# thread_dongle.net
KiCad netlist of a schematic drawn in EAGLE
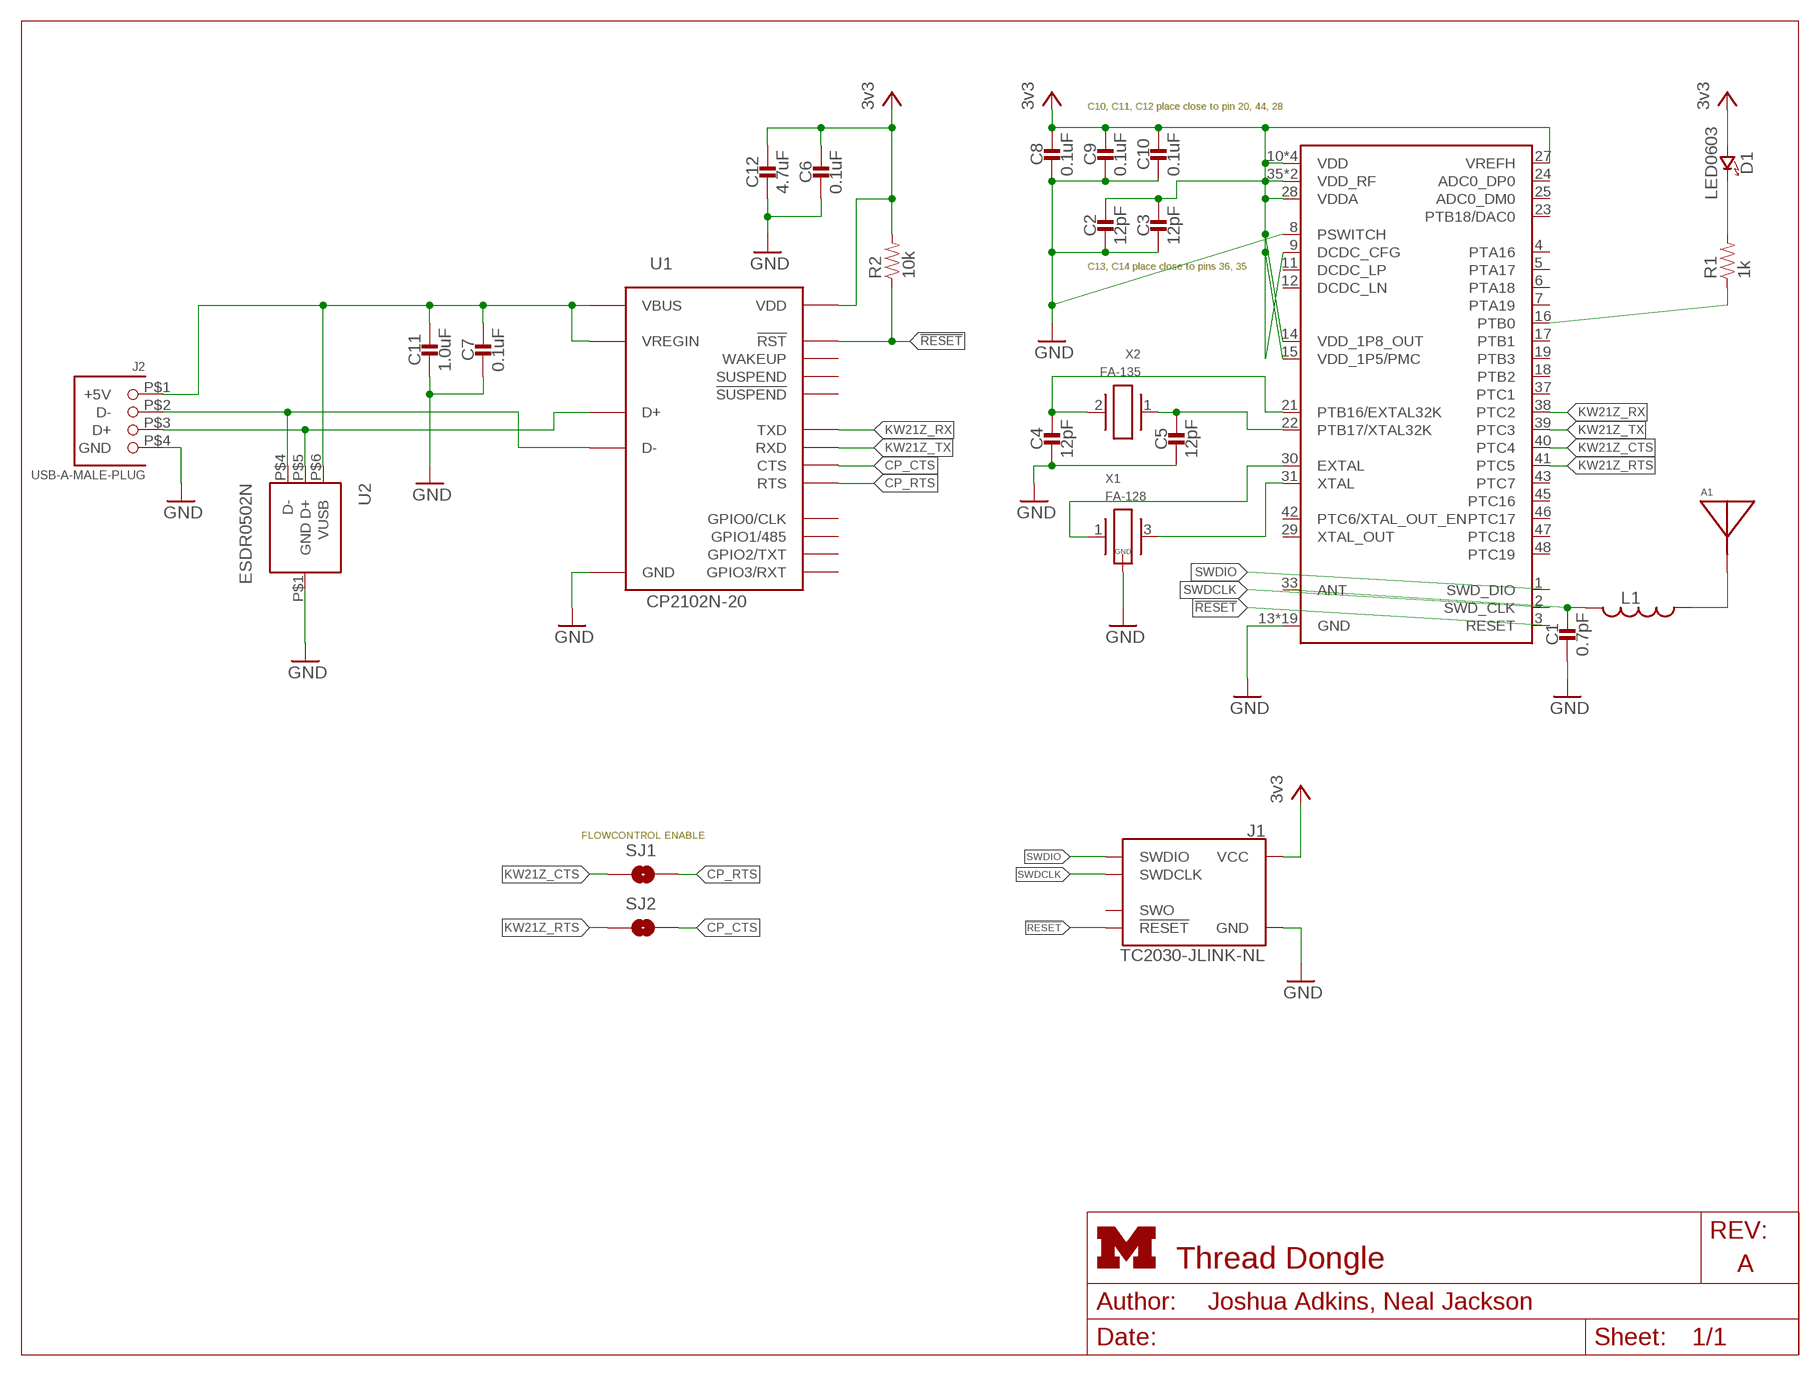
[diagram p0: schematic, sheet 1]

(export (version "E")
  (design (tool "Eeschema 10.0.6"))
  (components
    (comp (ref "A1")
      (value "AH212M")
      (footprint "eagle-import:AH212M")
      (libsource (lib "eagle-import") (part "AH212M"))
    )
    (comp (ref "C1")
      (value "0.7pF")
      (footprint "eagle-import:0402_CAP")
      (fields (field (name "MPN") "GRM1555C1HR70BA01D"))
      (libsource (lib "eagle-import") (part "CAPACITOR0402_CAP"))
    )
    (comp (ref "C2")
      (value "12pF")
      (footprint "eagle-import:0402_CAP")
      (fields (field (name "MPN") "GRM1555C1H120JA01D"))
      (libsource (lib "eagle-import") (part "CAPACITOR0402_CAP"))
    )
    (comp (ref "C3")
      (value "12pF")
      (footprint "eagle-import:0402_CAP")
      (fields (field (name "MPN") "GRM1555C1H120JA01D"))
      (libsource (lib "eagle-import") (part "CAPACITOR0402_CAP"))
    )
    (comp (ref "C4")
      (value "12pF")
      (footprint "eagle-import:0402_CAP")
      (fields (field (name "MPN") "GRM1555C1H120JA01D"))
      (libsource (lib "eagle-import") (part "CAPACITOR0402_CAP"))
    )
    (comp (ref "C5")
      (value "12pF")
      (footprint "eagle-import:0402_CAP")
      (fields (field (name "MPN") "GRM1555C1H120JA01D"))
      (libsource (lib "eagle-import") (part "CAPACITOR0402_CAP"))
    )
    (comp (ref "C6")
      (value "0.1uF")
      (footprint "eagle-import:0402_CAP")
      (fields (field (name "MPN") "LMK105BJ104KV-F"))
      (libsource (lib "eagle-import") (part "CAPACITOR0402_CAP"))
    )
    (comp (ref "C7")
      (value "0.1uF")
      (footprint "eagle-import:0402_CAP")
      (fields (field (name "MPN") "LMK105BJ104KV-F"))
      (libsource (lib "eagle-import") (part "CAPACITOR0402_CAP"))
    )
    (comp (ref "C8")
      (value "0.1uF")
      (footprint "eagle-import:0402_CAP")
      (fields (field (name "MPN") "LMK105BJ104KV-F"))
      (libsource (lib "eagle-import") (part "CAPACITOR0402_CAP"))
    )
    (comp (ref "C9")
      (value "0.1uF")
      (footprint "eagle-import:0402_CAP")
      (fields (field (name "MPN") "LMK105BJ104KV-F"))
      (libsource (lib "eagle-import") (part "CAPACITOR0402_CAP"))
    )
    (comp (ref "C10")
      (value "0.1uF")
      (footprint "eagle-import:0402_CAP")
      (fields (field (name "MPN") "LMK105BJ104KV-F"))
      (libsource (lib "eagle-import") (part "CAPACITOR0402_CAP"))
    )
    (comp (ref "C11")
      (value "1.0uF")
      (footprint "eagle-import:0402_CAP")
      (fields (field (name "MPN") "GRM155R61E105MA12D"))
      (libsource (lib "eagle-import") (part "CAPACITOR0402_CAP"))
    )
    (comp (ref "C12")
      (value "4.7uF")
      (footprint "eagle-import:0402_CAP")
      (fields (field (name "MPN") "GRM155R60J475ME47D"))
      (libsource (lib "eagle-import") (part "CAPACITOR0402_CAP"))
    )
    (comp (ref "D1")
      (value "LED0603")
      (footprint "eagle-import:LED-0603")
      (fields (field (name "MPN") "LTST-C194TBKT"))
      (libsource (lib "eagle-import") (part "LED0603"))
    )
    (comp (ref "J1")
      (value "TC2030-JLINK-NL")
      (footprint "eagle-import:TC2030-IDC-NL")
      (libsource (lib "eagle-import") (part "TC2030-JLINK-NL"))
    )
    (comp (ref "J2")
      (value "USB-A-MALE-PLUG")
      (footprint "eagle-import:USB_A_MALE_PLUG_CUI_UP2-AH")
      (fields (field (name "MANUFACTURER") "CUI") (field (name "MPN") "UP2-AH-1-TH"))
      (libsource (lib "eagle-import") (part "USB-A-MALE-PLUG"))
    )
    (comp (ref "L1")
      (value "INDUCTOR0402")
      (footprint "eagle-import:0402_CAP")
      (fields (field (name "MPN") "LQG15HS5N1S02D"))
      (libsource (lib "eagle-import") (part "INDUCTOR0402"))
    )
    (comp (ref "R1")
      (value "1k")
      (footprint "eagle-import:0402_RES")
      (fields (field (name "MPN") "RC0402JR-071KL"))
      (libsource (lib "eagle-import") (part "RESISTOR0402_RES"))
    )
    (comp (ref "R2")
      (value "10k")
      (footprint "eagle-import:0402_RES")
      (fields (field (name "MPN") "RC0402JR-0710KL"))
      (libsource (lib "eagle-import") (part "RESISTOR0402_RES"))
    )
    (comp (ref "SJ1")
      (value "SOLDERJUMPERNC")
      (footprint "eagle-import:SJ_2S_SMALL")
      (libsource (lib "eagle-import") (part "SOLDERJUMPERNC"))
    )
    (comp (ref "SJ2")
      (value "SOLDERJUMPERNC")
      (footprint "eagle-import:SJ_2S_SMALL")
      (libsource (lib "eagle-import") (part "SOLDERJUMPERNC"))
    )
    (comp (ref "U1")
      (value "CP2102N-20")
      (footprint "eagle-import:QFN-20-3MM")
      (fields (field (name "MANUFACTURER") "SiLabs") (field (name "MPN") "CP2102N-A01-GQFN20"))
      (libsource (lib "eagle-import") (part "CP2102N-20"))
    )
    (comp (ref "U2")
      (value "ESDR0502N")
      (footprint "eagle-import:UDFN-6")
      (libsource (lib "eagle-import") (part "ESDR0502N"))
    )
    (comp (ref "U3")
      (value "KW21Z")
      (footprint "eagle-import:LAMINATE-QFN-48-7MM")
      (fields (field (name "MPN") "MKW21Z256VHT4"))
      (libsource (lib "eagle-import") (part "KW21Z"))
    )
    (comp (ref "X1")
      (value "FA-128")
      (footprint "eagle-import:FA-128")
      (fields (field (name "MPN") "FA-128 32.0000MF20X-K5"))
      (libsource (lib "eagle-import") (part "FA-128"))
    )
    (comp (ref "X2")
      (value "FA-135")
      (footprint "eagle-import:FC-135")
      (fields (field (name "MPN") "FC-135 32.7680KA-AG3"))
      (libsource (lib "eagle-import") (part "FA-135"))
    )
  )
  (nets
    (net (code "1") (name "/~{RESET}") (class "Default")
      (node (ref "J1") (pin "3") (pinfunction "~{RESET}_3") (pintype "bidirectional"))
      (node (ref "R2") (pin "1") (pinfunction "1_1") (pintype "passive"))
      (node (ref "U1") (pin "9") (pinfunction "~{RST}_9") (pintype "bidirectional"))
      (node (ref "U3") (pin "3") (pinfunction "RESET_3") (pintype "bidirectional"))
    )
    (net (code "2") (name "3v3") (class "Default")
      (node (ref "C10") (pin "1") (pinfunction "1_1") (pintype "bidirectional"))
      (node (ref "C12") (pin "1") (pinfunction "1_1") (pintype "bidirectional"))
      (node (ref "C2") (pin "1") (pinfunction "1_1") (pintype "bidirectional"))
      (node (ref "C3") (pin "1") (pinfunction "1_1") (pintype "bidirectional"))
      (node (ref "C6") (pin "1") (pinfunction "1_1") (pintype "bidirectional"))
      (node (ref "C8") (pin "1") (pinfunction "1_1") (pintype "bidirectional"))
      (node (ref "C9") (pin "1") (pinfunction "1_1") (pintype "bidirectional"))
      (node (ref "D1") (pin "A") (pinfunction "ANODE_A") (pintype "bidirectional"))
      (node (ref "J1") (pin "1") (pinfunction "VCC_1") (pintype "bidirectional"))
      (node (ref "R2") (pin "2") (pinfunction "2_2") (pintype "passive"))
      (node (ref "U1") (pin "6") (pinfunction "VDD_6") (pintype "bidirectional"))
      (node (ref "U3") (pin "10") (pinfunction "VDD_10") (pintype "bidirectional"))
      (node (ref "U3") (pin "14") (pinfunction "VDD_1P8_OUT_14") (pintype "bidirectional"))
      (node (ref "U3") (pin "15") (pinfunction "VDD_1P5/PMC_15") (pintype "bidirectional"))
      (node (ref "U3") (pin "20") (pinfunction "VDD_20") (pintype "bidirectional"))
      (node (ref "U3") (pin "27") (pinfunction "VREFH_27") (pintype "bidirectional"))
      (node (ref "U3") (pin "28") (pinfunction "VDDA_28") (pintype "bidirectional"))
      (node (ref "U3") (pin "32") (pinfunction "VDD_32") (pintype "bidirectional"))
      (node (ref "U3") (pin "35") (pinfunction "VDD_RF_35") (pintype "bidirectional"))
      (node (ref "U3") (pin "36") (pinfunction "VDD_RF_36") (pintype "bidirectional"))
      (node (ref "U3") (pin "44") (pinfunction "VDD_44") (pintype "bidirectional"))
      (node (ref "U3") (pin "9") (pinfunction "DCDC_CFG_9") (pintype "bidirectional"))
    )
    (net (code "3") (name "CP_CTS") (class "Default")
      (node (ref "SJ2") (pin "2") (pinfunction "2_2") (pintype "passive"))
      (node (ref "U1") (pin "15") (pinfunction "CTS_15") (pintype "bidirectional"))
    )
    (net (code "4") (name "CP_RTS") (class "Default")
      (node (ref "SJ1") (pin "2") (pinfunction "2_2") (pintype "passive"))
      (node (ref "U1") (pin "16") (pinfunction "RTS_16") (pintype "bidirectional"))
    )
    (net (code "5") (name "GND") (class "Default")
      (node (ref "C1") (pin "2") (pinfunction "2_2") (pintype "bidirectional"))
      (node (ref "C10") (pin "2") (pinfunction "2_2") (pintype "bidirectional"))
      (node (ref "C11") (pin "2") (pinfunction "2_2") (pintype "bidirectional"))
      (node (ref "C12") (pin "2") (pinfunction "2_2") (pintype "bidirectional"))
      (node (ref "C2") (pin "2") (pinfunction "2_2") (pintype "bidirectional"))
      (node (ref "C3") (pin "2") (pinfunction "2_2") (pintype "bidirectional"))
      (node (ref "C4") (pin "2") (pinfunction "2_2") (pintype "bidirectional"))
      (node (ref "C5") (pin "2") (pinfunction "2_2") (pintype "bidirectional"))
      (node (ref "C6") (pin "2") (pinfunction "2_2") (pintype "bidirectional"))
      (node (ref "C7") (pin "2") (pinfunction "2_2") (pintype "bidirectional"))
      (node (ref "C8") (pin "2") (pinfunction "2_2") (pintype "bidirectional"))
      (node (ref "C9") (pin "2") (pinfunction "2_2") (pintype "bidirectional"))
      (node (ref "J1") (pin "5") (pinfunction "GND_5") (pintype "bidirectional"))
      (node (ref "J2") (pin "P$4") (pinfunction "GND_P$4") (pintype "bidirectional"))
      (node (ref "U1") (pin "12") (pinfunction "GND_12") (pintype "bidirectional"))
      (node (ref "U1") (pin "3") (pinfunction "GND_3") (pintype "bidirectional"))
      (node (ref "U1") (pin "P$1") (pinfunction "GND_P$1") (pintype "bidirectional"))
      (node (ref "U2") (pin "P$1") (pinfunction "GND_P$1") (pintype "bidirectional"))
      (node (ref "U3") (pin "13") (pinfunction "GND_13") (pintype "bidirectional"))
      (node (ref "U3") (pin "26") (pinfunction "GND_26") (pintype "bidirectional"))
      (node (ref "U3") (pin "34") (pinfunction "GND_34") (pintype "bidirectional"))
      (node (ref "U3") (pin "49") (pinfunction "GND_49") (pintype "bidirectional"))
      (node (ref "U3") (pin "50") (pinfunction "GND_50") (pintype "bidirectional"))
      (node (ref "U3") (pin "51") (pinfunction "GND_51") (pintype "bidirectional"))
      (node (ref "U3") (pin "52") (pinfunction "GND_52") (pintype "bidirectional"))
      (node (ref "U3") (pin "53") (pinfunction "GND_53") (pintype "bidirectional"))
      (node (ref "U3") (pin "54") (pinfunction "GND_54") (pintype "bidirectional"))
      (node (ref "U3") (pin "55") (pinfunction "GND_55") (pintype "bidirectional"))
      (node (ref "U3") (pin "56") (pinfunction "GND_56") (pintype "bidirectional"))
      (node (ref "U3") (pin "57") (pinfunction "GND_57") (pintype "bidirectional"))
      (node (ref "U3") (pin "58") (pinfunction "GND_58") (pintype "bidirectional"))
      (node (ref "U3") (pin "59") (pinfunction "GND_59") (pintype "bidirectional"))
      (node (ref "U3") (pin "60") (pinfunction "GND_60") (pintype "bidirectional"))
      (node (ref "U3") (pin "61") (pinfunction "GND_61") (pintype "bidirectional"))
      (node (ref "U3") (pin "62") (pinfunction "GND_62") (pintype "bidirectional"))
      (node (ref "U3") (pin "63") (pinfunction "GND_63") (pintype "bidirectional"))
      (node (ref "U3") (pin "64") (pinfunction "GND_64") (pintype "bidirectional"))
      (node (ref "U3") (pin "8") (pinfunction "PSWITCH_8") (pintype "bidirectional"))
      (node (ref "X1") (pin "2") (pinfunction "GND_2") (pintype "bidirectional"))
      (node (ref "X1") (pin "4") (pinfunction "GND_4") (pintype "bidirectional"))
    )
    (net (code "6") (name "KW21Z_CTS") (class "Default")
      (node (ref "SJ1") (pin "1") (pinfunction "1_1") (pintype "passive"))
      (node (ref "U3") (pin "40") (pinfunction "PTC4_40") (pintype "bidirectional"))
    )
    (net (code "7") (name "KW21Z_RTS") (class "Default")
      (node (ref "SJ2") (pin "1") (pinfunction "1_1") (pintype "passive"))
      (node (ref "U3") (pin "41") (pinfunction "PTC5_41") (pintype "bidirectional"))
    )
    (net (code "8") (name "KW21Z_RX") (class "Default")
      (node (ref "U1") (pin "18") (pinfunction "TXD_18") (pintype "bidirectional"))
      (node (ref "U3") (pin "38") (pinfunction "PTC2_38") (pintype "bidirectional"))
    )
    (net (code "9") (name "KW21Z_TX") (class "Default")
      (node (ref "U1") (pin "17") (pinfunction "RXD_17") (pintype "bidirectional"))
      (node (ref "U3") (pin "39") (pinfunction "PTC3_39") (pintype "bidirectional"))
    )
    (net (code "10") (name "Net-(A1-ANTENNA)") (class "Default")
      (node (ref "A1") (pin "P1") (pinfunction "ANTENNA_P1") (pintype "bidirectional"))
      (node (ref "L1") (pin "1") (pinfunction "1_1") (pintype "bidirectional"))
    )
    (net (code "11") (name "Net-(D1-CATHODE)") (class "Default")
      (node (ref "D1") (pin "C") (pinfunction "CATHODE_C") (pintype "bidirectional"))
      (node (ref "R1") (pin "2") (pinfunction "2_2") (pintype "passive"))
    )
    (net (code "12") (name "Net-(J2-+5V)") (class "Default")
      (node (ref "C11") (pin "1") (pinfunction "1_1") (pintype "bidirectional"))
      (node (ref "C7") (pin "1") (pinfunction "1_1") (pintype "bidirectional"))
      (node (ref "J2") (pin "P$1") (pinfunction "+5V_P$1") (pintype "bidirectional"))
      (node (ref "U1") (pin "7") (pinfunction "VREGIN_7") (pintype "bidirectional"))
      (node (ref "U1") (pin "8") (pinfunction "VBUS_8") (pintype "bidirectional"))
      (node (ref "U2") (pin "P$6") (pinfunction "VUSB_P$6") (pintype "bidirectional"))
    )
    (net (code "13") (name "Net-(J2-D+)") (class "Default")
      (node (ref "J2") (pin "P$3") (pinfunction "D+_P$3") (pintype "bidirectional"))
      (node (ref "U1") (pin "4") (pinfunction "D+_4") (pintype "bidirectional"))
      (node (ref "U2") (pin "P$5") (pinfunction "D+_P$5") (pintype "bidirectional"))
    )
    (net (code "14") (name "Net-(J2-D-)") (class "Default")
      (node (ref "J2") (pin "P$2") (pinfunction "D-_P$2") (pintype "bidirectional"))
      (node (ref "U1") (pin "5") (pinfunction "D-_5") (pintype "bidirectional"))
      (node (ref "U2") (pin "P$4") (pinfunction "D-_P$4") (pintype "bidirectional"))
    )
    (net (code "15") (name "Net-(U3-ANT)") (class "Default")
      (node (ref "C1") (pin "1") (pinfunction "1_1") (pintype "bidirectional"))
      (node (ref "L1") (pin "2") (pinfunction "2_2") (pintype "bidirectional"))
      (node (ref "U3") (pin "33") (pinfunction "ANT_33") (pintype "bidirectional"))
    )
    (net (code "16") (name "Net-(U3-EXTAL)") (class "Default")
      (node (ref "U3") (pin "30") (pinfunction "EXTAL_30") (pintype "bidirectional"))
      (node (ref "X1") (pin "1") (pinfunction "1_1") (pintype "bidirectional"))
    )
    (net (code "17") (name "Net-(U3-PTB0)") (class "Default")
      (node (ref "R1") (pin "1") (pinfunction "1_1") (pintype "passive"))
      (node (ref "U3") (pin "16") (pinfunction "PTB0_16") (pintype "bidirectional"))
    )
    (net (code "18") (name "Net-(U3-PTB16{slash}EXTAL32K)") (class "Default")
      (node (ref "C4") (pin "1") (pinfunction "1_1") (pintype "bidirectional"))
      (node (ref "U3") (pin "21") (pinfunction "PTB16/EXTAL32K_21") (pintype "bidirectional"))
      (node (ref "X2") (pin "2") (pinfunction "2_2") (pintype "bidirectional"))
    )
    (net (code "19") (name "Net-(U3-PTB17{slash}XTAL32K)") (class "Default")
      (node (ref "C5") (pin "1") (pinfunction "1_1") (pintype "bidirectional"))
      (node (ref "U3") (pin "22") (pinfunction "PTB17/XTAL32K_22") (pintype "bidirectional"))
      (node (ref "X2") (pin "1") (pinfunction "1_1") (pintype "bidirectional"))
    )
    (net (code "20") (name "Net-(U3-XTAL)") (class "Default")
      (node (ref "U3") (pin "31") (pinfunction "XTAL_31") (pintype "bidirectional"))
      (node (ref "X1") (pin "3") (pinfunction "2_3") (pintype "bidirectional"))
    )
    (net (code "21") (name "SWDCLK") (class "Default")
      (node (ref "J1") (pin "4") (pinfunction "SWDCLK_4") (pintype "bidirectional"))
      (node (ref "U3") (pin "2") (pinfunction "SWD_CLK_2") (pintype "bidirectional"))
    )
    (net (code "22") (name "SWDIO") (class "Default")
      (node (ref "J1") (pin "2") (pinfunction "SWDIO_2") (pintype "bidirectional"))
      (node (ref "U3") (pin "1") (pinfunction "SWD_DIO_1") (pintype "bidirectional"))
    )
    (net (code "23") (name "unconnected-(J1-SWO-Pad6)") (class "Default")
      (node (ref "J1") (pin "6") (pinfunction "SWO_6") (pintype "bidirectional"))
    )
    (net (code "24") (name "unconnected-(U1-GPIO0{slash}CLK-Pad2)") (class "Default")
      (node (ref "U1") (pin "2") (pinfunction "GPIO0/CLK_2") (pintype "bidirectional"))
    )
    (net (code "25") (name "unconnected-(U1-GPIO1{slash}485-Pad1)") (class "Default")
      (node (ref "U1") (pin "1") (pinfunction "GPIO1/485_1") (pintype "bidirectional"))
    )
    (net (code "26") (name "unconnected-(U1-GPIO2{slash}TXT-Pad20)") (class "Default")
      (node (ref "U1") (pin "20") (pinfunction "GPIO2/TXT_20") (pintype "bidirectional"))
    )
    (net (code "27") (name "unconnected-(U1-GPIO3{slash}RXT-Pad19)") (class "Default")
      (node (ref "U1") (pin "19") (pinfunction "GPIO3/RXT_19") (pintype "bidirectional"))
    )
    (net (code "28") (name "unconnected-(U1-SUSPEND-Pad14)") (class "Default")
      (node (ref "U1") (pin "14") (pinfunction "SUSPEND_14") (pintype "bidirectional"))
    )
    (net (code "29") (name "unconnected-(U1-WAKEUP-Pad13)") (class "Default")
      (node (ref "U1") (pin "13") (pinfunction "WAKEUP_13") (pintype "bidirectional"))
    )
    (net (code "30") (name "unconnected-(U1-~{SUSPEND}-Pad11)") (class "Default")
      (node (ref "U1") (pin "11") (pinfunction "~{SUSPEND}_11") (pintype "bidirectional"))
    )
    (net (code "31") (name "unconnected-(U3-ADC0_DM0-Pad25)") (class "Default")
      (node (ref "U3") (pin "25") (pinfunction "ADC0_DM0_25") (pintype "bidirectional"))
    )
    (net (code "32") (name "unconnected-(U3-ADC0_DP0-Pad24)") (class "Default")
      (node (ref "U3") (pin "24") (pinfunction "ADC0_DP0_24") (pintype "bidirectional"))
    )
    (net (code "33") (name "unconnected-(U3-DCDC_LN-Pad12)") (class "Default")
      (node (ref "U3") (pin "12") (pinfunction "DCDC_LN_12") (pintype "bidirectional"))
    )
    (net (code "34") (name "unconnected-(U3-DCDC_LP-Pad11)") (class "Default")
      (node (ref "U3") (pin "11") (pinfunction "DCDC_LP_11") (pintype "bidirectional"))
    )
    (net (code "35") (name "unconnected-(U3-PTA16-Pad4)") (class "Default")
      (node (ref "U3") (pin "4") (pinfunction "PTA16_4") (pintype "bidirectional"))
    )
    (net (code "36") (name "unconnected-(U3-PTA17-Pad5)") (class "Default")
      (node (ref "U3") (pin "5") (pinfunction "PTA17_5") (pintype "bidirectional"))
    )
    (net (code "37") (name "unconnected-(U3-PTA18-Pad6)") (class "Default")
      (node (ref "U3") (pin "6") (pinfunction "PTA18_6") (pintype "bidirectional"))
    )
    (net (code "38") (name "unconnected-(U3-PTA19-Pad7)") (class "Default")
      (node (ref "U3") (pin "7") (pinfunction "PTA19_7") (pintype "bidirectional"))
    )
    (net (code "39") (name "unconnected-(U3-PTB1-Pad17)") (class "Default")
      (node (ref "U3") (pin "17") (pinfunction "PTB1_17") (pintype "bidirectional"))
    )
    (net (code "40") (name "unconnected-(U3-PTB2-Pad18)") (class "Default")
      (node (ref "U3") (pin "18") (pinfunction "PTB2_18") (pintype "bidirectional"))
    )
    (net (code "41") (name "unconnected-(U3-PTB3-Pad19)") (class "Default")
      (node (ref "U3") (pin "19") (pinfunction "PTB3_19") (pintype "bidirectional"))
    )
    (net (code "42") (name "unconnected-(U3-PTB18{slash}DAC0-Pad23)") (class "Default")
      (node (ref "U3") (pin "23") (pinfunction "PTB18/DAC0_23") (pintype "bidirectional"))
    )
    (net (code "43") (name "unconnected-(U3-PTC1-Pad37)") (class "Default")
      (node (ref "U3") (pin "37") (pinfunction "PTC1_37") (pintype "bidirectional"))
    )
    (net (code "44") (name "unconnected-(U3-PTC6{slash}XTAL_OUT_EN-Pad42)") (class "Default")
      (node (ref "U3") (pin "42") (pinfunction "PTC6/XTAL_OUT_EN_42") (pintype "bidirectional"))
    )
    (net (code "45") (name "unconnected-(U3-PTC7-Pad43)") (class "Default")
      (node (ref "U3") (pin "43") (pinfunction "PTC7_43") (pintype "bidirectional"))
    )
    (net (code "46") (name "unconnected-(U3-PTC16-Pad45)") (class "Default")
      (node (ref "U3") (pin "45") (pinfunction "PTC16_45") (pintype "bidirectional"))
    )
    (net (code "47") (name "unconnected-(U3-PTC17-Pad46)") (class "Default")
      (node (ref "U3") (pin "46") (pinfunction "PTC17_46") (pintype "bidirectional"))
    )
    (net (code "48") (name "unconnected-(U3-PTC18-Pad47)") (class "Default")
      (node (ref "U3") (pin "47") (pinfunction "PTC18_47") (pintype "bidirectional"))
    )
    (net (code "49") (name "unconnected-(U3-PTC19-Pad48)") (class "Default")
      (node (ref "U3") (pin "48") (pinfunction "PTC19_48") (pintype "bidirectional"))
    )
    (net (code "50") (name "unconnected-(U3-XTAL_OUT-Pad29)") (class "Default")
      (node (ref "U3") (pin "29") (pinfunction "XTAL_OUT_29") (pintype "bidirectional"))
    )
  )
)
